# Funky_v3_r3.net
KiCad netlist of a schematic drawn in EAGLE
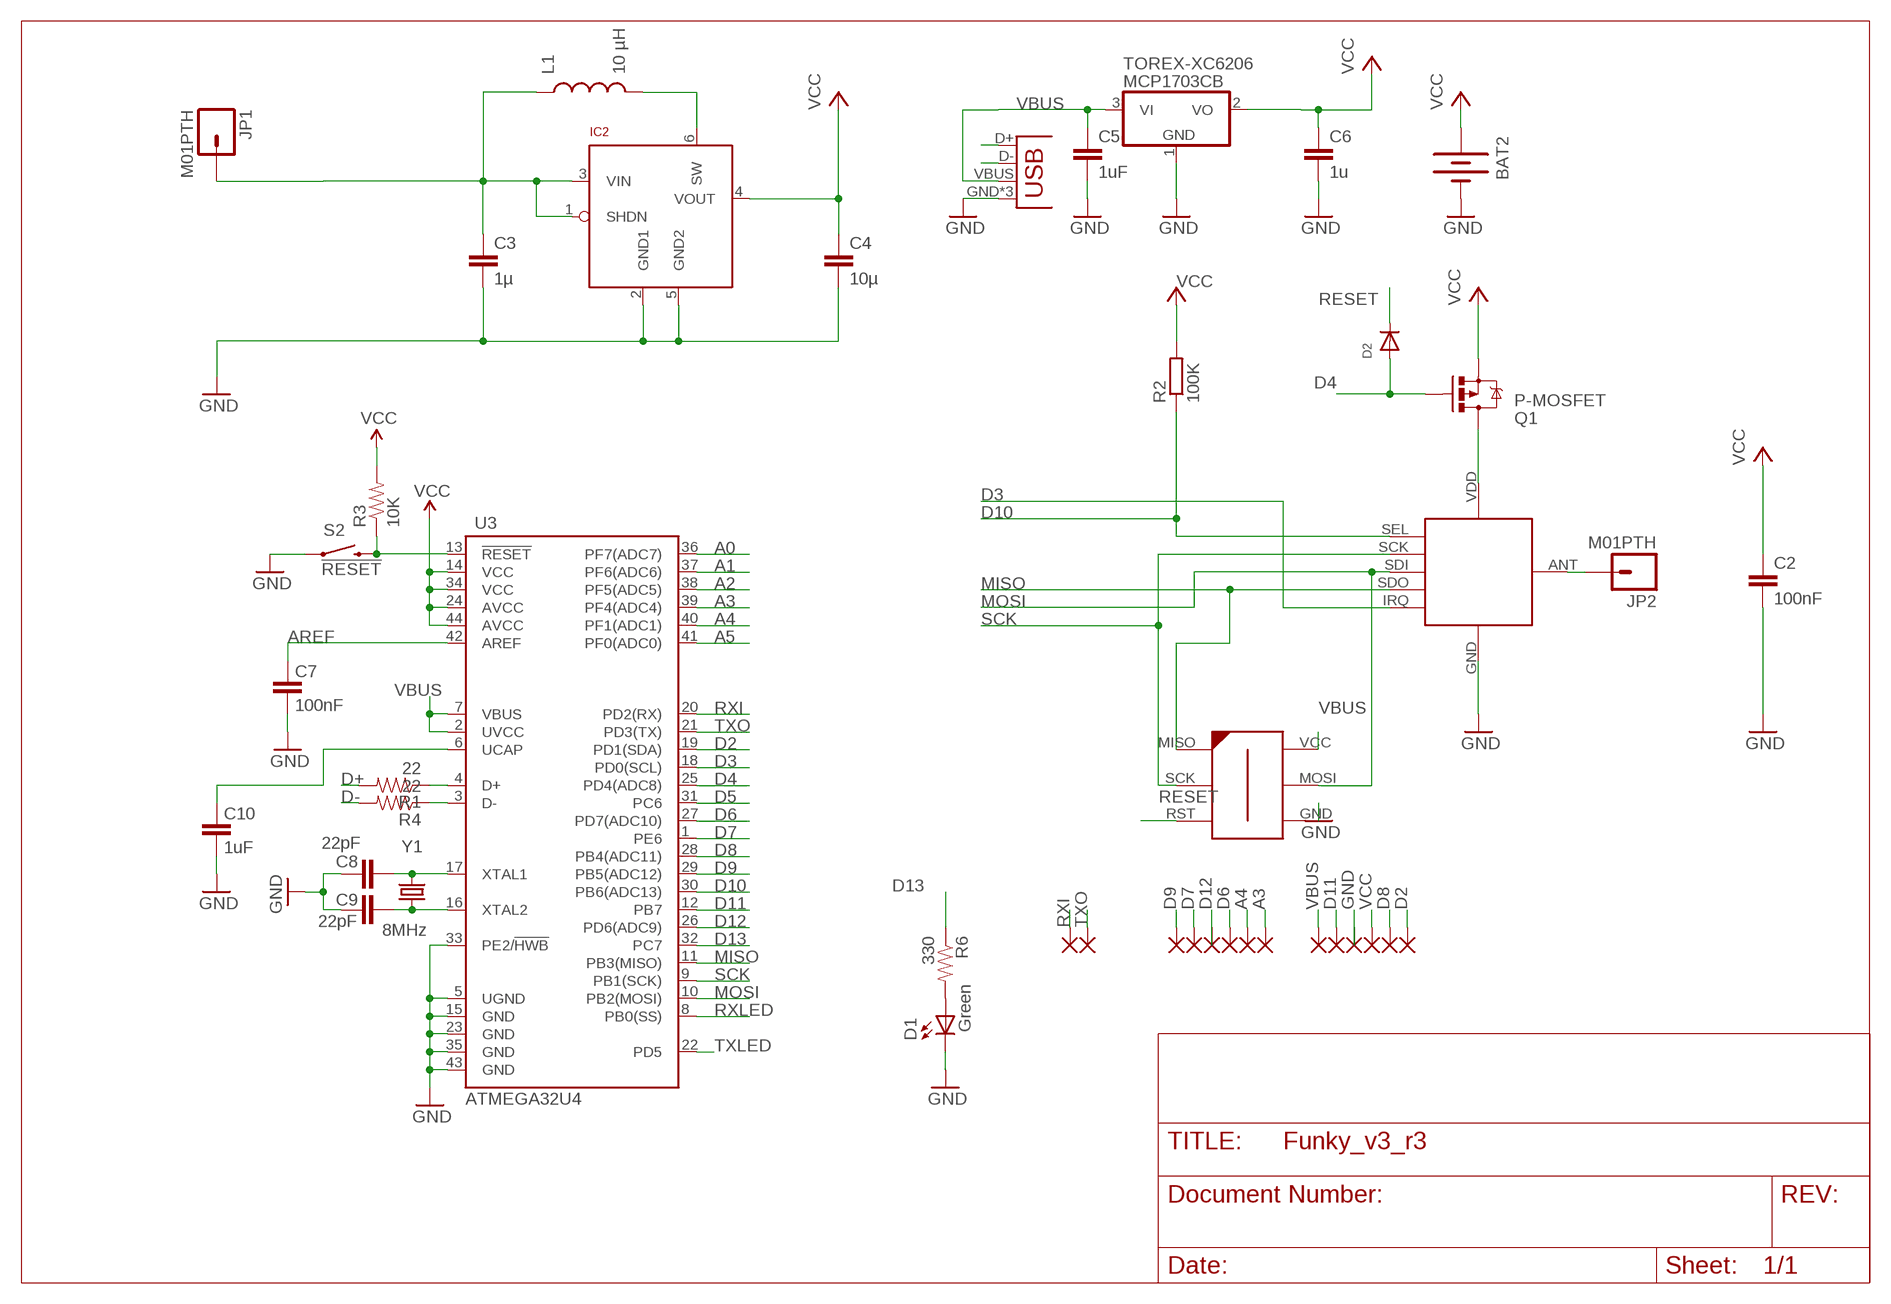
[diagram p0: schematic, sheet 1]

(export (version "E")
  (design (tool "Eeschema 10.0.6"))
  (components
    (comp (ref "BAT2")
      (value "BATTERY20PTH")
      (footprint "eagle-import:BATTCOM_20MM_PTH")
      (libsource (lib "eagle-import") (part "BATTERY20PTH"))
    )
    (comp (ref "C2")
      (value "100nF")
      (footprint "eagle-import:C0603K")
      (libsource (lib "eagle-import") (part "C-EUC0603K"))
    )
    (comp (ref "C3")
      (value "1µ")
      (footprint "eagle-import:0603-CAP")
      (libsource (lib "eagle-import") (part "CAP0603-CAP"))
    )
    (comp (ref "C4")
      (value "10µ")
      (footprint "eagle-import:0805")
      (libsource (lib "eagle-import") (part "CAP0805"))
    )
    (comp (ref "C5")
      (value "1uF")
      (footprint "eagle-import:C0603K")
      (libsource (lib "eagle-import") (part "C-EUC0603K"))
    )
    (comp (ref "C6")
      (value "1u")
      (footprint "eagle-import:C0603K")
      (libsource (lib "eagle-import") (part "C-EUC0603K"))
    )
    (comp (ref "C7")
      (value "100nF")
      (footprint "eagle-import:0402-CAP")
      (libsource (lib "eagle-import") (part "CAP0402-CAP"))
    )
    (comp (ref "C8")
      (value "22pF")
      (footprint "eagle-import:0402-CAP")
      (libsource (lib "eagle-import") (part "CAP0402-CAP"))
    )
    (comp (ref "C9")
      (value "22pF")
      (footprint "eagle-import:0402-CAP")
      (libsource (lib "eagle-import") (part "CAP0402-CAP"))
    )
    (comp (ref "C10")
      (value "1uF")
      (footprint "eagle-import:0402-CAP")
      (libsource (lib "eagle-import") (part "CAP0402-CAP"))
    )
    (comp (ref "D1")
      (value "Green")
      (footprint "eagle-import:LED-0603")
      (libsource (lib "eagle-import") (part "LED0603"))
    )
    (comp (ref "D2")
      (value "DIODESOD-323F")
      (footprint "eagle-import:SOD-323F")
      (libsource (lib "eagle-import") (part "DIODESOD-323F"))
    )
    (comp (ref "IC2")
      (value "LTC3525")
      (footprint "eagle-import:SC70")
      (libsource (lib "eagle-import") (part "LTC3525"))
    )
    (comp (ref "JP1")
      (value "M01PTH")
      (footprint "eagle-import:1X01")
      (libsource (lib "eagle-import") (part "M01PTH"))
    )
    (comp (ref "JP2")
      (value "M01PTH")
      (footprint "eagle-import:1X01")
      (libsource (lib "eagle-import") (part "M01PTH"))
    )
    (comp (ref "JP3")
      (value "USB-MICROB")
      (footprint "eagle-import:USB-MICROB")
      (libsource (lib "eagle-import") (part "USB-MICROB"))
    )
    (comp (ref "L1")
      (value "10 µH")
      (footprint "eagle-import:1210")
      (libsource (lib "eagle-import") (part "INDUCTOR1210"))
    )
    (comp (ref "PAD1")
      (value "SMD2")
      (footprint "eagle-import:SMD1,27-2,54")
      (libsource (lib "eagle-import") (part "SMD2"))
    )
    (comp (ref "PAD2")
      (value "SMD2")
      (footprint "eagle-import:SMD1,27-2,54")
      (libsource (lib "eagle-import") (part "SMD2"))
    )
    (comp (ref "PAD3")
      (value "SMD2")
      (footprint "eagle-import:SMD1,27-2,54")
      (libsource (lib "eagle-import") (part "SMD2"))
    )
    (comp (ref "PAD4")
      (value "SMD2")
      (footprint "eagle-import:SMD1,27-2,54")
      (libsource (lib "eagle-import") (part "SMD2"))
    )
    (comp (ref "PAD5")
      (value "SMD2")
      (footprint "eagle-import:SMD1,27-2,54")
      (libsource (lib "eagle-import") (part "SMD2"))
    )
    (comp (ref "PAD6")
      (value "SMD2")
      (footprint "eagle-import:SMD1,27-2,54")
      (libsource (lib "eagle-import") (part "SMD2"))
    )
    (comp (ref "PAD7")
      (value "SMD2")
      (footprint "eagle-import:SMD1,27-2,54")
      (libsource (lib "eagle-import") (part "SMD2"))
    )
    (comp (ref "PAD8")
      (value "SMD2")
      (footprint "eagle-import:SMD1,27-2,54")
      (libsource (lib "eagle-import") (part "SMD2"))
    )
    (comp (ref "PAD9")
      (value "SMD2")
      (footprint "eagle-import:SMD1,27-2,54")
      (libsource (lib "eagle-import") (part "SMD2"))
    )
    (comp (ref "PAD10")
      (value "SMD2")
      (footprint "eagle-import:SMD1,27-2,54")
      (libsource (lib "eagle-import") (part "SMD2"))
    )
    (comp (ref "PAD11")
      (value "SMD2")
      (footprint "eagle-import:SMD1,27-2,54")
      (libsource (lib "eagle-import") (part "SMD2"))
    )
    (comp (ref "PAD12")
      (value "SMD2")
      (footprint "eagle-import:SMD1,27-2,54")
      (libsource (lib "eagle-import") (part "SMD2"))
    )
    (comp (ref "PAD13")
      (value "SMD2")
      (footprint "eagle-import:SMD1,27-2,54")
      (libsource (lib "eagle-import") (part "SMD2"))
    )
    (comp (ref "PAD14")
      (value "SMD2")
      (footprint "eagle-import:SMD1,27-2,54")
      (libsource (lib "eagle-import") (part "SMD2"))
    )
    (comp (ref "Q1")
      (value "P-MOSFET")
      (footprint "eagle-import:SOT23")
      (libsource (lib "eagle-import") (part "MOSFET-PCHANNEL"))
    )
    (comp (ref "R1")
      (value "22")
      (footprint "eagle-import:0402-RES")
      (libsource (lib "eagle-import") (part "RESISTOR0402-RES"))
    )
    (comp (ref "R2")
      (value "100K")
      (footprint "eagle-import:R0402")
      (libsource (lib "eagle-import") (part "R-EU_R0402"))
    )
    (comp (ref "R3")
      (value "10K")
      (footprint "eagle-import:0402-RES")
      (libsource (lib "eagle-import") (part "RESISTOR0402-RES"))
    )
    (comp (ref "R4")
      (value "22")
      (footprint "eagle-import:0402-RES")
      (libsource (lib "eagle-import") (part "RESISTOR0402-RES"))
    )
    (comp (ref "R6")
      (value "330")
      (footprint "eagle-import:0402-RES")
      (libsource (lib "eagle-import") (part "RESISTOR0402-RES"))
    )
    (comp (ref "RFM12B1")
      (value "RFM12B_MINPADS")
      (footprint "eagle-import:RFM12B-MINPADS")
      (libsource (lib "eagle-import") (part "RFM12B_MINPADS"))
    )
    (comp (ref "S2")
      (value "!RESET")
      (footprint "eagle-import:TACTILE_SWITCH_SMD")
      (libsource (lib "eagle-import") (part "SWITCH-MOMENTARY-2SMD"))
    )
    (comp (ref "TOREX-XC6206")
      (value "MCP1703CB")
      (footprint "eagle-import:SOT23")
      (libsource (lib "eagle-import") (part "MCP1703CB"))
    )
    (comp (ref "U$2")
      (value "AVR-ISP-6-EDGE")
      (footprint "eagle-import:6PAD_ISP")
      (libsource (lib "eagle-import") (part "AVR-ISP-6-EDGE"))
    )
    (comp (ref "U3")
      (value "ATMEGA32U4")
      (footprint "eagle-import:QFN-44-NOPAD")
      (libsource (lib "eagle-import") (part "ATMEGA32U4QFN2"))
    )
    (comp (ref "Y1")
      (value "8MHz")
      (footprint "eagle-import:CRYSTAL-SMD-5X3")
      (libsource (lib "eagle-import") (part "CRYSTAL5X3"))
    )
  )
  (nets
    (net (code "1") (name "/A0") (class "Default")
      (node (ref "U3") (pin "36") (pinfunction "PF7(ADC7)_36") (pintype "bidirectional"))
    )
    (net (code "2") (name "/A1") (class "Default")
      (node (ref "U3") (pin "37") (pinfunction "PF6(ADC6)_37") (pintype "bidirectional"))
    )
    (net (code "3") (name "/A2") (class "Default")
      (node (ref "U3") (pin "38") (pinfunction "PF5(ADC5)_38") (pintype "bidirectional"))
    )
    (net (code "4") (name "/A3") (class "Default")
      (node (ref "PAD6") (pin "1") (pinfunction "P_1") (pintype "passive"))
      (node (ref "U3") (pin "39") (pinfunction "PF4(ADC4)_39") (pintype "bidirectional"))
    )
    (net (code "5") (name "/A4") (class "Default")
      (node (ref "PAD5") (pin "1") (pinfunction "P_1") (pintype "passive"))
      (node (ref "U3") (pin "40") (pinfunction "PF1(ADC1)_40") (pintype "bidirectional"))
    )
    (net (code "6") (name "/A5") (class "Default")
      (node (ref "U3") (pin "41") (pinfunction "PF0(ADC0)_41") (pintype "bidirectional"))
    )
    (net (code "7") (name "/AREF") (class "Default")
      (node (ref "C7") (pin "2") (pinfunction "2_2") (pintype "passive"))
      (node (ref "U3") (pin "42") (pinfunction "AREF_42") (pintype "bidirectional"))
    )
    (net (code "8") (name "/D+") (class "Default")
      (node (ref "JP3") (pin "D+") (pinfunction "D+_D+") (pintype "bidirectional"))
      (node (ref "R1") (pin "2") (pinfunction "2_2") (pintype "passive"))
    )
    (net (code "9") (name "/D-") (class "Default")
      (node (ref "JP3") (pin "D-") (pinfunction "D-_D-") (pintype "bidirectional"))
      (node (ref "R4") (pin "2") (pinfunction "2_2") (pintype "passive"))
    )
    (net (code "10") (name "/D2") (class "Default")
      (node (ref "PAD12") (pin "1") (pinfunction "P_1") (pintype "passive"))
      (node (ref "U3") (pin "19") (pinfunction "PD1(SDA)_19") (pintype "bidirectional"))
    )
    (net (code "11") (name "/D3") (class "Default")
      (node (ref "RFM12B1") (pin "IRQ") (pinfunction "IRQ_IRQ") (pintype "bidirectional"))
      (node (ref "U3") (pin "18") (pinfunction "PD0(SCL)_18") (pintype "bidirectional"))
    )
    (net (code "12") (name "/D4") (class "Default")
      (node (ref "D2") (pin "A") (pinfunction "A_A") (pintype "passive"))
      (node (ref "Q1") (pin "1") (pinfunction "G_1") (pintype "passive"))
      (node (ref "U3") (pin "25") (pinfunction "PD4(ADC8)_25") (pintype "bidirectional"))
    )
    (net (code "13") (name "/D5") (class "Default")
      (node (ref "U3") (pin "31") (pinfunction "PC6_31") (pintype "bidirectional"))
    )
    (net (code "14") (name "/D6") (class "Default")
      (node (ref "PAD4") (pin "1") (pinfunction "P_1") (pintype "passive"))
      (node (ref "U3") (pin "27") (pinfunction "PD7(ADC10)_27") (pintype "bidirectional"))
    )
    (net (code "15") (name "/D7") (class "Default")
      (node (ref "PAD2") (pin "1") (pinfunction "P_1") (pintype "passive"))
      (node (ref "U3") (pin "1") (pinfunction "PE6_1") (pintype "bidirectional"))
    )
    (net (code "16") (name "/D8") (class "Default")
      (node (ref "PAD11") (pin "1") (pinfunction "P_1") (pintype "passive"))
      (node (ref "U3") (pin "28") (pinfunction "PB4(ADC11)_28") (pintype "bidirectional"))
    )
    (net (code "17") (name "/D9") (class "Default")
      (node (ref "PAD1") (pin "1") (pinfunction "P_1") (pintype "passive"))
      (node (ref "U3") (pin "29") (pinfunction "PB5(ADC12)_29") (pintype "bidirectional"))
    )
    (net (code "18") (name "/D10") (class "Default")
      (node (ref "R2") (pin "1") (pinfunction "1_1") (pintype "passive"))
      (node (ref "RFM12B1") (pin "SEL") (pinfunction "SEL_SEL") (pintype "bidirectional"))
      (node (ref "U3") (pin "30") (pinfunction "PB6(ADC13)_30") (pintype "bidirectional"))
    )
    (net (code "19") (name "/D11") (class "Default")
      (node (ref "PAD7") (pin "1") (pinfunction "P_1") (pintype "passive"))
      (node (ref "U3") (pin "12") (pinfunction "PB7_12") (pintype "bidirectional"))
    )
    (net (code "20") (name "/D12") (class "Default")
      (node (ref "PAD3") (pin "1") (pinfunction "P_1") (pintype "passive"))
      (node (ref "U3") (pin "26") (pinfunction "PD6(ADC9)_26") (pintype "bidirectional"))
    )
    (net (code "21") (name "/D13") (class "Default")
      (node (ref "R6") (pin "1") (pinfunction "1_1") (pintype "passive"))
      (node (ref "U3") (pin "32") (pinfunction "PC7_32") (pintype "bidirectional"))
    )
    (net (code "22") (name "/MISO") (class "Default")
      (node (ref "RFM12B1") (pin "SDO") (pinfunction "SDO/MISO_SDO") (pintype "bidirectional"))
      (node (ref "U$2") (pin "MISO") (pinfunction "P$1_MISO") (pintype "bidirectional"))
      (node (ref "U3") (pin "11") (pinfunction "PB3(MISO)_11") (pintype "bidirectional"))
    )
    (net (code "23") (name "/MOSI") (class "Default")
      (node (ref "RFM12B1") (pin "SDI") (pinfunction "SDI/MOSI_SDI") (pintype "bidirectional"))
      (node (ref "U$2") (pin "MOSI") (pinfunction "P$5_MOSI") (pintype "bidirectional"))
      (node (ref "U3") (pin "10") (pinfunction "PB2(MOSI)_10") (pintype "bidirectional"))
    )
    (net (code "24") (name "/RESET") (class "Default")
      (node (ref "D2") (pin "C") (pinfunction "C_C") (pintype "passive"))
      (node (ref "R3") (pin "1") (pinfunction "1_1") (pintype "passive"))
      (node (ref "S2") (pin "3") (pinfunction "2_3") (pintype "passive"))
      (node (ref "U$2") (pin "RST") (pinfunction "P$3_RST") (pintype "bidirectional"))
      (node (ref "U3") (pin "13") (pinfunction "~{RESET}_13") (pintype "bidirectional"))
    )
    (net (code "25") (name "/RXI") (class "Default")
      (node (ref "PAD14") (pin "1") (pinfunction "P_1") (pintype "passive"))
      (node (ref "U3") (pin "20") (pinfunction "PD2(RX)_20") (pintype "bidirectional"))
    )
    (net (code "26") (name "/RXLED") (class "Default")
      (node (ref "U3") (pin "8") (pinfunction "PB0(SS)_8") (pintype "bidirectional"))
    )
    (net (code "27") (name "/SCK") (class "Default")
      (node (ref "RFM12B1") (pin "SCK") (pinfunction "SCK_SCK") (pintype "bidirectional"))
      (node (ref "U$2") (pin "SCK") (pinfunction "P$2_SCK") (pintype "bidirectional"))
      (node (ref "U3") (pin "9") (pinfunction "PB1(SCK)_9") (pintype "bidirectional"))
    )
    (net (code "28") (name "/TXLED") (class "Default")
      (node (ref "U3") (pin "22") (pinfunction "PD5_22") (pintype "bidirectional"))
    )
    (net (code "29") (name "/TXO") (class "Default")
      (node (ref "PAD13") (pin "1") (pinfunction "P_1") (pintype "passive"))
      (node (ref "U3") (pin "21") (pinfunction "PD3(TX)_21") (pintype "bidirectional"))
    )
    (net (code "30") (name "/VBUS") (class "Default")
      (node (ref "C5") (pin "1") (pinfunction "1_1") (pintype "passive"))
      (node (ref "JP3") (pin "VBUS") (pinfunction "VBUS_VBUS") (pintype "bidirectional"))
      (node (ref "PAD8") (pin "1") (pinfunction "P_1") (pintype "passive"))
      (node (ref "TOREX-XC6206") (pin "3") (pinfunction "VI_3") (pintype "input"))
      (node (ref "U$2") (pin "VCC") (pinfunction "P$6_VCC") (pintype "bidirectional"))
      (node (ref "U3") (pin "2") (pinfunction "UVCC_2") (pintype "bidirectional"))
      (node (ref "U3") (pin "7") (pinfunction "VBUS_7") (pintype "bidirectional"))
    )
    (net (code "31") (name "GND") (class "Default")
      (node (ref "BAT2") (pin "2") (pinfunction "-_2") (pintype "power_in"))
      (node (ref "C10") (pin "1") (pinfunction "1_1") (pintype "passive"))
      (node (ref "C2") (pin "2") (pinfunction "2_2") (pintype "passive"))
      (node (ref "C3") (pin "2") (pinfunction "2_2") (pintype "passive"))
      (node (ref "C4") (pin "2") (pinfunction "2_2") (pintype "passive"))
      (node (ref "C5") (pin "2") (pinfunction "2_2") (pintype "passive"))
      (node (ref "C6") (pin "2") (pinfunction "2_2") (pintype "passive"))
      (node (ref "C7") (pin "1") (pinfunction "1_1") (pintype "passive"))
      (node (ref "C8") (pin "2") (pinfunction "2_2") (pintype "passive"))
      (node (ref "C9") (pin "2") (pinfunction "2_2") (pintype "passive"))
      (node (ref "D1") (pin "C") (pinfunction "C_C") (pintype "passive"))
      (node (ref "IC2") (pin "2") (pinfunction "GND1_2") (pintype "power_in"))
      (node (ref "IC2") (pin "5") (pinfunction "GND2_5") (pintype "power_in"))
      (node (ref "JP3") (pin "GND") (pinfunction "GND_GND") (pintype "bidirectional"))
      (node (ref "JP3") (pin "MT1") (pinfunction "GND_MT1") (pintype "bidirectional"))
      (node (ref "JP3") (pin "MT2") (pinfunction "GND_MT2") (pintype "bidirectional"))
      (node (ref "PAD9") (pin "1") (pinfunction "P_1") (pintype "passive"))
      (node (ref "RFM12B1") (pin "GND") (pinfunction "GND_GND") (pintype "bidirectional"))
      (node (ref "S2") (pin "1") (pinfunction "1_1") (pintype "passive"))
      (node (ref "TOREX-XC6206") (pin "1") (pinfunction "GND_1") (pintype "passive"))
      (node (ref "U$2") (pin "GND") (pinfunction "P$4_GND") (pintype "bidirectional"))
      (node (ref "U3") (pin "15") (pinfunction "GND_15") (pintype "bidirectional"))
      (node (ref "U3") (pin "23") (pinfunction "GND_23") (pintype "bidirectional"))
      (node (ref "U3") (pin "33") (pinfunction "PE2/~{HWB}_33") (pintype "bidirectional"))
      (node (ref "U3") (pin "35") (pinfunction "GND_35") (pintype "bidirectional"))
      (node (ref "U3") (pin "43") (pinfunction "GND_43") (pintype "bidirectional"))
      (node (ref "U3") (pin "5") (pinfunction "UGND_5") (pintype "bidirectional"))
    )
    (net (code "32") (name "Net-(D1-PadA)") (class "Default")
      (node (ref "D1") (pin "A") (pinfunction "A_A") (pintype "passive"))
      (node (ref "R6") (pin "2") (pinfunction "2_2") (pintype "passive"))
    )
    (net (code "33") (name "Net-(IC2-SHDN)") (class "Default")
      (node (ref "C3") (pin "1") (pinfunction "1_1") (pintype "passive"))
      (node (ref "IC2") (pin "1") (pinfunction "SHDN_1") (pintype "input"))
      (node (ref "IC2") (pin "3") (pinfunction "VIN_3") (pintype "tri_state"))
      (node (ref "JP1") (pin "1") (pinfunction "1_1") (pintype "passive"))
      (node (ref "L1") (pin "1") (pinfunction "1_1") (pintype "passive"))
    )
    (net (code "34") (name "Net-(IC2-SW)") (class "Default")
      (node (ref "IC2") (pin "6") (pinfunction "SW_6") (pintype "power_in"))
      (node (ref "L1") (pin "2") (pinfunction "2_2") (pintype "passive"))
    )
    (net (code "35") (name "Net-(JP2-Pad1)") (class "Default")
      (node (ref "JP2") (pin "1") (pinfunction "1_1") (pintype "passive"))
      (node (ref "RFM12B1") (pin "ANT") (pinfunction "ANT_ANT") (pintype "bidirectional"))
    )
    (net (code "36") (name "Net-(Q1-D)") (class "Default")
      (node (ref "Q1") (pin "3") (pinfunction "D_3") (pintype "passive"))
      (node (ref "RFM12B1") (pin "VDD") (pinfunction "VDD_VDD") (pintype "bidirectional"))
    )
    (net (code "37") (name "Net-(U3-D+)") (class "Default")
      (node (ref "R1") (pin "1") (pinfunction "1_1") (pintype "passive"))
      (node (ref "U3") (pin "4") (pinfunction "D+_4") (pintype "bidirectional"))
    )
    (net (code "38") (name "Net-(U3-D-)") (class "Default")
      (node (ref "R4") (pin "1") (pinfunction "1_1") (pintype "passive"))
      (node (ref "U3") (pin "3") (pinfunction "D-_3") (pintype "bidirectional"))
    )
    (net (code "39") (name "Net-(U3-UCAP)") (class "Default")
      (node (ref "C10") (pin "2") (pinfunction "2_2") (pintype "passive"))
      (node (ref "U3") (pin "6") (pinfunction "UCAP_6") (pintype "bidirectional"))
    )
    (net (code "40") (name "Net-(U3-XTAL1)") (class "Default")
      (node (ref "C8") (pin "1") (pinfunction "1_1") (pintype "passive"))
      (node (ref "U3") (pin "17") (pinfunction "XTAL1_17") (pintype "bidirectional"))
      (node (ref "Y1") (pin "3") (pinfunction "2_3") (pintype "passive"))
    )
    (net (code "41") (name "Net-(U3-XTAL2)") (class "Default")
      (node (ref "C9") (pin "1") (pinfunction "1_1") (pintype "passive"))
      (node (ref "U3") (pin "16") (pinfunction "XTAL2_16") (pintype "bidirectional"))
      (node (ref "Y1") (pin "1") (pinfunction "1_1") (pintype "passive"))
    )
    (net (code "42") (name "VCC") (class "Default")
      (node (ref "BAT2") (pin "1") (pinfunction "+_1") (pintype "power_in"))
      (node (ref "C2") (pin "1") (pinfunction "1_1") (pintype "passive"))
      (node (ref "C4") (pin "1") (pinfunction "1_1") (pintype "passive"))
      (node (ref "C6") (pin "1") (pinfunction "1_1") (pintype "passive"))
      (node (ref "IC2") (pin "4") (pinfunction "VOUT_4") (pintype "power_in"))
      (node (ref "PAD10") (pin "1") (pinfunction "P_1") (pintype "passive"))
      (node (ref "Q1") (pin "2") (pinfunction "S_2") (pintype "passive"))
      (node (ref "R2") (pin "2") (pinfunction "2_2") (pintype "passive"))
      (node (ref "R3") (pin "2") (pinfunction "2_2") (pintype "passive"))
      (node (ref "TOREX-XC6206") (pin "2") (pinfunction "VO_2") (pintype "passive"))
      (node (ref "U3") (pin "14") (pinfunction "VCC_14") (pintype "bidirectional"))
      (node (ref "U3") (pin "24") (pinfunction "AVCC_24") (pintype "bidirectional"))
      (node (ref "U3") (pin "34") (pinfunction "VCC_34") (pintype "bidirectional"))
      (node (ref "U3") (pin "44") (pinfunction "AVCC_44") (pintype "bidirectional"))
    )
  )
)
